# Qwiic_AS3935_Lightning_Detector.net
KiCad netlist of a schematic drawn in EAGLE
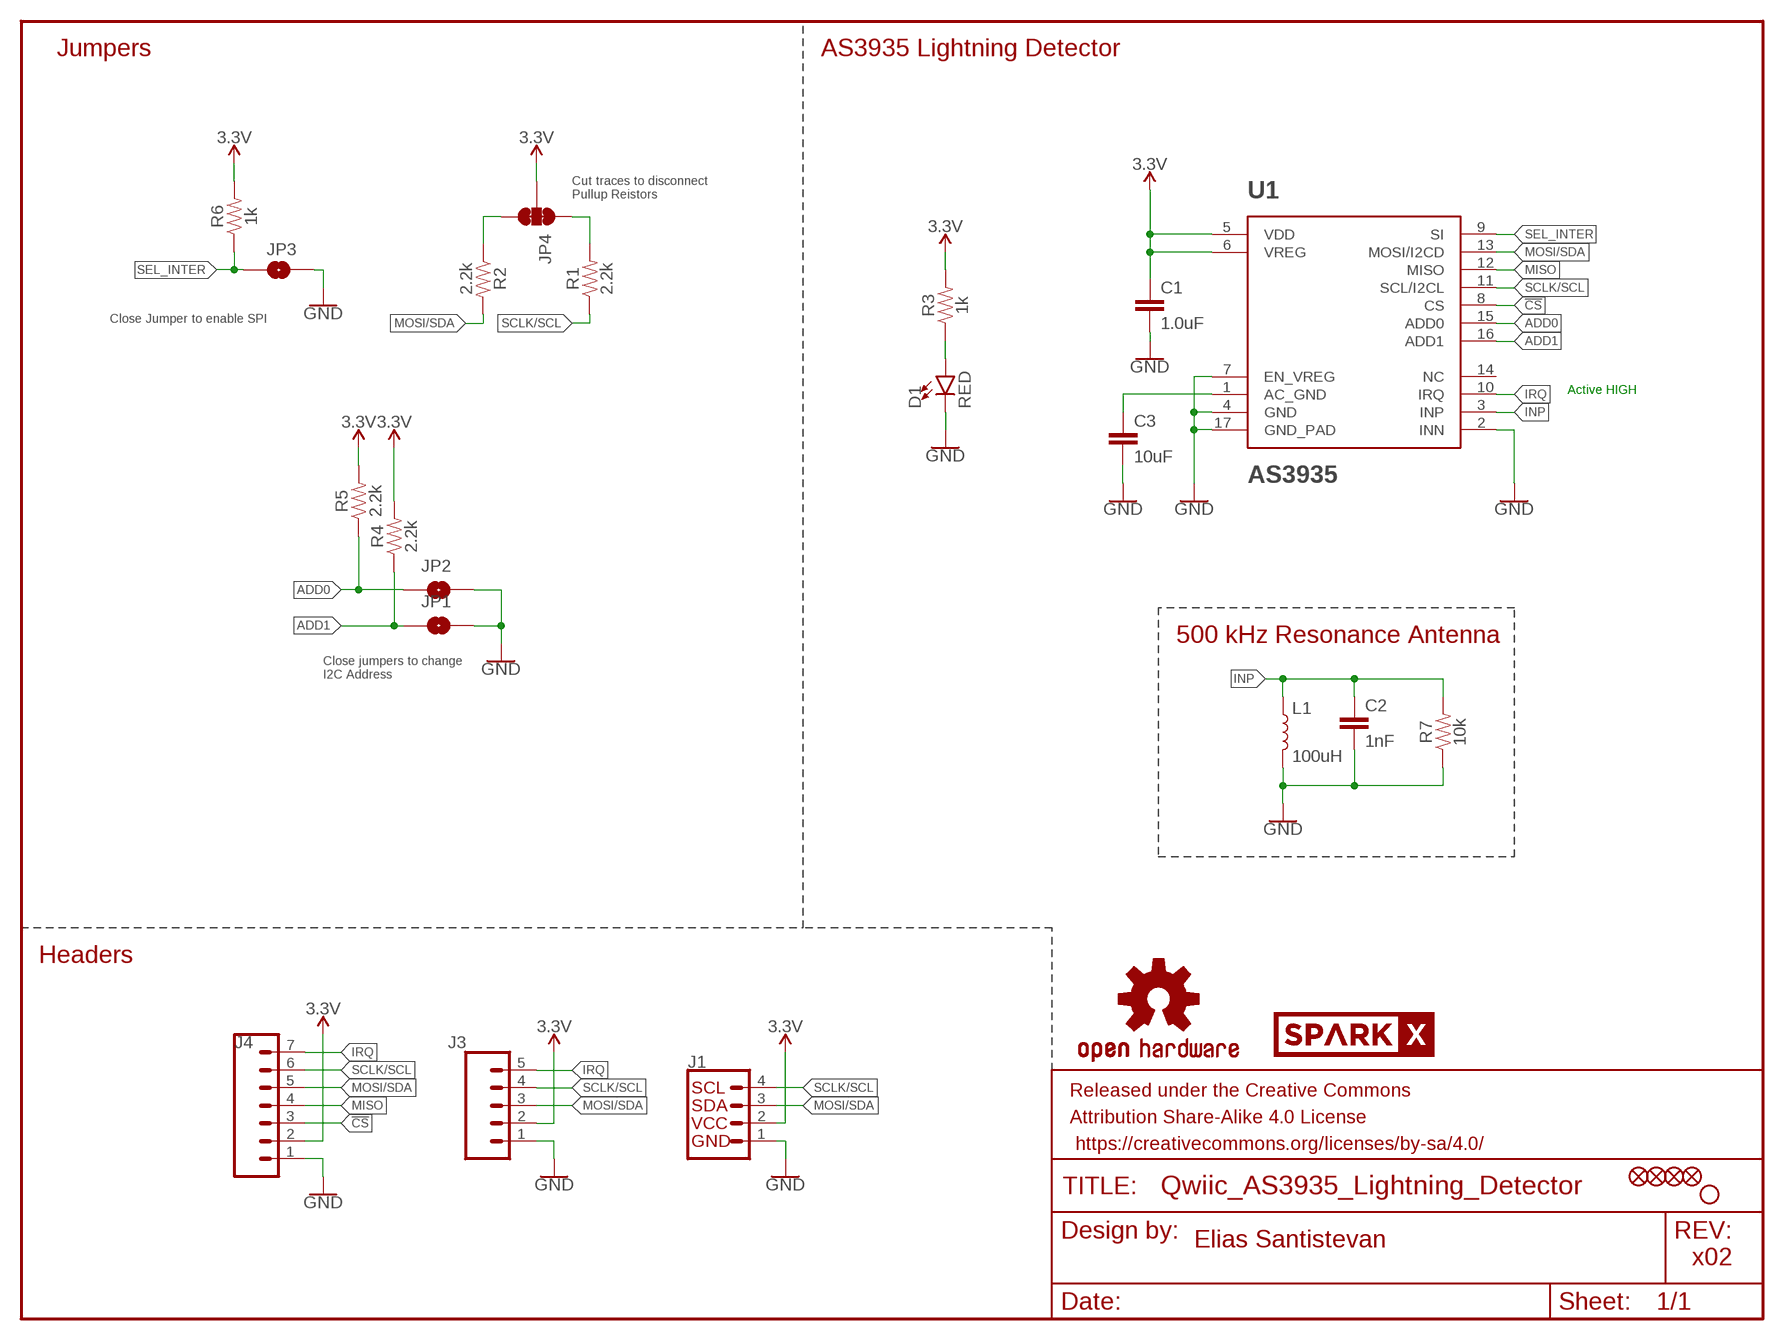
[diagram p0: schematic, sheet 1]

(export (version "E")
  (design (tool "Eeschema 10.0.6"))
  (components
    (comp (ref "C1")
      (value "1.0uF")
      (footprint "eagle-import:0603")
      (libsource (lib "eagle-import") (part "1.0UF-0603-16V-10%"))
    )
    (comp (ref "C2")
      (value "1nF")
      (footprint "eagle-import:0603")
      (libsource (lib "eagle-import") (part "1.0NF/1000PF-0603-50V-10%"))
    )
    (comp (ref "C3")
      (value "10uF")
      (footprint "eagle-import:0603")
      (libsource (lib "eagle-import") (part "10UF-0603-6.3V-20%"))
    )
    (comp (ref "D1")
      (value "RED")
      (footprint "eagle-import:LED-0603")
      (libsource (lib "eagle-import") (part "LED-RED0603"))
    )
    (comp (ref "FD1")
      (value "FIDUCIAL1X2")
      (footprint "eagle-import:FIDUCIAL-1X2")
      (libsource (lib "eagle-import") (part "FIDUCIAL1X2"))
    )
    (comp (ref "FD2")
      (value "FIDUCIAL1X2")
      (footprint "eagle-import:FIDUCIAL-1X2")
      (libsource (lib "eagle-import") (part "FIDUCIAL1X2"))
    )
    (comp (ref "FD3")
      (value "FIDUCIAL1X2")
      (footprint "eagle-import:FIDUCIAL-1X2")
      (libsource (lib "eagle-import") (part "FIDUCIAL1X2"))
    )
    (comp (ref "FD4")
      (value "FIDUCIAL1X2")
      (footprint "eagle-import:FIDUCIAL-1X2")
      (libsource (lib "eagle-import") (part "FIDUCIAL1X2"))
    )
    (comp (ref "FRAME1")
      (value "FRAME-LETTER")
      (footprint "eagle-import:CREATIVE_COMMONS")
      (libsource (lib "eagle-import") (part "FRAME-LETTER"))
    )
    (comp (ref "H1")
      (value "STAND-OFFTIGHT")
      (footprint "eagle-import:STAND-OFF-TIGHT")
      (libsource (lib "eagle-import") (part "STAND-OFFTIGHT"))
    )
    (comp (ref "J1")
      (value "QWIIC_CONNECTORJS-1MM")
      (footprint "eagle-import:1X04_1MM_RA")
      (libsource (lib "eagle-import") (part "QWIIC_CONNECTORJS-1MM"))
    )
    (comp (ref "J3")
      (value "CONN_05NO_SILK")
      (footprint "eagle-import:1X05_NO_SILK")
      (libsource (lib "eagle-import") (part "CONN_05NO_SILK"))
    )
    (comp (ref "J4")
      (value "CONN_07NO_SILK")
      (footprint "eagle-import:1X07_NO_SILK")
      (libsource (lib "eagle-import") (part "CONN_07NO_SILK"))
    )
    (comp (ref "JP1")
      (value "JUMPER-SMT_2_NO_SILK")
      (footprint "eagle-import:SMT-JUMPER_2_NO_SILK")
      (libsource (lib "eagle-import") (part "JUMPER-SMT_2_NO_SILK"))
    )
    (comp (ref "JP2")
      (value "JUMPER-SMT_2_NO_SILK")
      (footprint "eagle-import:SMT-JUMPER_2_NO_SILK")
      (libsource (lib "eagle-import") (part "JUMPER-SMT_2_NO_SILK"))
    )
    (comp (ref "JP3")
      (value "JUMPER-SMT_2_NO_SILK")
      (footprint "eagle-import:SMT-JUMPER_2_NO_SILK")
      (libsource (lib "eagle-import") (part "JUMPER-SMT_2_NO_SILK"))
    )
    (comp (ref "JP4")
      (value "JUMPER-SMT_3_2-NC_TRACE_SILK")
      (footprint "eagle-import:SMT-JUMPER_3_2-NC_TRACE_SILK")
      (libsource (lib "eagle-import") (part "JUMPER-SMT_3_2-NC_TRACE_SILK"))
    )
    (comp (ref "L1")
      (value "100uH")
      (footprint "eagle-import:MA5532-AE")
      (libsource (lib "eagle-import") (part "MA5532-AE"))
    )
    (comp (ref "LOGO1")
      (value "OSHW-LOGOS")
      (footprint "eagle-import:OSHW-LOGO-S")
      (libsource (lib "eagle-import") (part "OSHW-LOGOS"))
    )
    (comp (ref "R1")
      (value "2.2k")
      (footprint "eagle-import:0603")
      (libsource (lib "eagle-import") (part "2.2KOHM-0603-1/10W-1%"))
    )
    (comp (ref "R2")
      (value "2.2k")
      (footprint "eagle-import:0603")
      (libsource (lib "eagle-import") (part "2.2KOHM-0603-1/10W-1%"))
    )
    (comp (ref "R3")
      (value "1k")
      (footprint "eagle-import:0603")
      (libsource (lib "eagle-import") (part "1KOHM-0603-1/10W-1%"))
    )
    (comp (ref "R4")
      (value "2.2k")
      (footprint "eagle-import:0603")
      (libsource (lib "eagle-import") (part "2.2KOHM-0603-1/10W-1%"))
    )
    (comp (ref "R5")
      (value "2.2k")
      (footprint "eagle-import:0603")
      (libsource (lib "eagle-import") (part "2.2KOHM-0603-1/10W-1%"))
    )
    (comp (ref "R6")
      (value "1k")
      (footprint "eagle-import:0603")
      (libsource (lib "eagle-import") (part "1KOHM-0603-1/10W-1%"))
    )
    (comp (ref "R7")
      (value "10k")
      (footprint "eagle-import:0603")
      (libsource (lib "eagle-import") (part "10KOHM-0603-1/10W-1%"))
    )
    (comp (ref "U$1")
      (value "SPARKX-LOGO2")
      (footprint "eagle-import:SPARKX-TINY")
      (libsource (lib "eagle-import") (part "SPARKX-LOGO2"))
    )
    (comp (ref "U1")
      (value "AS3935")
      (footprint "eagle-import:16LD_MLPQ")
      (libsource (lib "eagle-import") (part "AS3935QFN"))
    )
  )
  (nets
    (net (code "1") (name "/~{CS}") (class "Default")
      (node (ref "J4") (pin "3") (pinfunction "3_3") (pintype "passive"))
      (node (ref "U1") (pin "8") (pinfunction "CS_8") (pintype "input"))
    )
    (net (code "2") (name "3.3V") (class "Default")
      (node (ref "C1") (pin "1") (pinfunction "1_1") (pintype "passive"))
      (node (ref "J1") (pin "2") (pinfunction "2_2") (pintype "power_in"))
      (node (ref "J3") (pin "2") (pinfunction "2_2") (pintype "passive"))
      (node (ref "J4") (pin "2") (pinfunction "2_2") (pintype "passive"))
      (node (ref "JP4") (pin "2") (pinfunction "2_2") (pintype "passive"))
      (node (ref "R3") (pin "2") (pinfunction "2_2") (pintype "passive"))
      (node (ref "R4") (pin "2") (pinfunction "2_2") (pintype "passive"))
      (node (ref "R5") (pin "2") (pinfunction "2_2") (pintype "passive"))
      (node (ref "R6") (pin "2") (pinfunction "2_2") (pintype "passive"))
      (node (ref "U1") (pin "5") (pinfunction "VDD_5") (pintype "power_in"))
      (node (ref "U1") (pin "6") (pinfunction "VREG_6") (pintype "power_in"))
    )
    (net (code "3") (name "ADD0") (class "Default")
      (node (ref "JP2") (pin "1") (pinfunction "1_1") (pintype "passive"))
      (node (ref "R5") (pin "1") (pinfunction "1_1") (pintype "passive"))
      (node (ref "U1") (pin "15") (pinfunction "ADD0_15") (pintype "input"))
    )
    (net (code "4") (name "ADD1") (class "Default")
      (node (ref "JP1") (pin "1") (pinfunction "1_1") (pintype "passive"))
      (node (ref "R4") (pin "1") (pinfunction "1_1") (pintype "passive"))
      (node (ref "U1") (pin "16") (pinfunction "ADD1_16") (pintype "input"))
    )
    (net (code "5") (name "GND") (class "Default")
      (node (ref "C1") (pin "2") (pinfunction "2_2") (pintype "passive"))
      (node (ref "C2") (pin "2") (pinfunction "2_2") (pintype "passive"))
      (node (ref "C3") (pin "2") (pinfunction "2_2") (pintype "passive"))
      (node (ref "D1") (pin "C") (pinfunction "C_C") (pintype "passive"))
      (node (ref "J1") (pin "1") (pinfunction "1_1") (pintype "power_in"))
      (node (ref "J3") (pin "1") (pinfunction "1_1") (pintype "passive"))
      (node (ref "J4") (pin "1") (pinfunction "1_1") (pintype "passive"))
      (node (ref "JP1") (pin "2") (pinfunction "2_2") (pintype "passive"))
      (node (ref "JP2") (pin "2") (pinfunction "2_2") (pintype "passive"))
      (node (ref "JP3") (pin "2") (pinfunction "2_2") (pintype "passive"))
      (node (ref "L1") (pin "2") (pinfunction "2_2") (pintype "passive"))
      (node (ref "R7") (pin "1") (pinfunction "1_1") (pintype "passive"))
      (node (ref "U1") (pin "17") (pinfunction "GND_PAD_17") (pintype "power_in"))
      (node (ref "U1") (pin "2") (pinfunction "INN_2") (pintype "bidirectional"))
      (node (ref "U1") (pin "4") (pinfunction "GND_4") (pintype "power_in"))
      (node (ref "U1") (pin "7") (pinfunction "EN_VREG_7") (pintype "bidirectional"))
    )
    (net (code "6") (name "INP") (class "Default")
      (node (ref "C2") (pin "1") (pinfunction "1_1") (pintype "passive"))
      (node (ref "L1") (pin "1") (pinfunction "1_1") (pintype "passive"))
      (node (ref "R7") (pin "2") (pinfunction "2_2") (pintype "passive"))
      (node (ref "U1") (pin "3") (pinfunction "INP_3") (pintype "bidirectional"))
    )
    (net (code "7") (name "IRQ") (class "Default")
      (node (ref "J3") (pin "5") (pinfunction "5_5") (pintype "passive"))
      (node (ref "J4") (pin "7") (pinfunction "7_7") (pintype "passive"))
      (node (ref "U1") (pin "10") (pinfunction "IRQ_10") (pintype "bidirectional"))
    )
    (net (code "8") (name "MISO") (class "Default")
      (node (ref "J4") (pin "4") (pinfunction "4_4") (pintype "passive"))
      (node (ref "U1") (pin "12") (pinfunction "MISO_12") (pintype "output"))
    )
    (net (code "9") (name "MOSI{slash}SDA") (class "Default")
      (node (ref "J1") (pin "3") (pinfunction "3_3") (pintype "passive"))
      (node (ref "J3") (pin "3") (pinfunction "3_3") (pintype "passive"))
      (node (ref "J4") (pin "5") (pinfunction "5_5") (pintype "passive"))
      (node (ref "R2") (pin "2") (pinfunction "2_2") (pintype "passive"))
      (node (ref "U1") (pin "13") (pinfunction "MOSI/I2CD_13") (pintype "input"))
    )
    (net (code "10") (name "Net-(D1-PadA)") (class "Default")
      (node (ref "D1") (pin "A") (pinfunction "A_A") (pintype "passive"))
      (node (ref "R3") (pin "1") (pinfunction "1_1") (pintype "passive"))
    )
    (net (code "11") (name "Net-(JP4-Pad1)") (class "Default")
      (node (ref "JP4") (pin "1") (pinfunction "1_1") (pintype "passive"))
      (node (ref "R1") (pin "2") (pinfunction "2_2") (pintype "passive"))
    )
    (net (code "12") (name "Net-(JP4-Pad3)") (class "Default")
      (node (ref "JP4") (pin "3") (pinfunction "3_3") (pintype "passive"))
      (node (ref "R2") (pin "1") (pinfunction "1_1") (pintype "passive"))
    )
    (net (code "13") (name "Net-(U1-AC_GND)") (class "Default")
      (node (ref "C3") (pin "1") (pinfunction "1_1") (pintype "passive"))
      (node (ref "U1") (pin "1") (pinfunction "AC_GND_1") (pintype "power_in"))
    )
    (net (code "14") (name "SCLK{slash}SCL") (class "Default")
      (node (ref "J1") (pin "4") (pinfunction "4_4") (pintype "passive"))
      (node (ref "J3") (pin "4") (pinfunction "4_4") (pintype "passive"))
      (node (ref "J4") (pin "6") (pinfunction "6_6") (pintype "passive"))
      (node (ref "R1") (pin "1") (pinfunction "1_1") (pintype "passive"))
      (node (ref "U1") (pin "11") (pinfunction "SCL/I2CL_11") (pintype "input"))
    )
    (net (code "15") (name "SEL_INTER") (class "Default")
      (node (ref "JP3") (pin "1") (pinfunction "1_1") (pintype "passive"))
      (node (ref "R6") (pin "1") (pinfunction "1_1") (pintype "passive"))
      (node (ref "U1") (pin "9") (pinfunction "SI_9") (pintype "input"))
    )
    (net (code "16") (name "unconnected-(U1-NC-Pad14)") (class "Default")
      (node (ref "U1") (pin "14") (pinfunction "NC_14") (pintype "no_connect"))
    )
  )
)
